# sensorNodev5.net
KiCad netlist of a schematic drawn in EAGLE
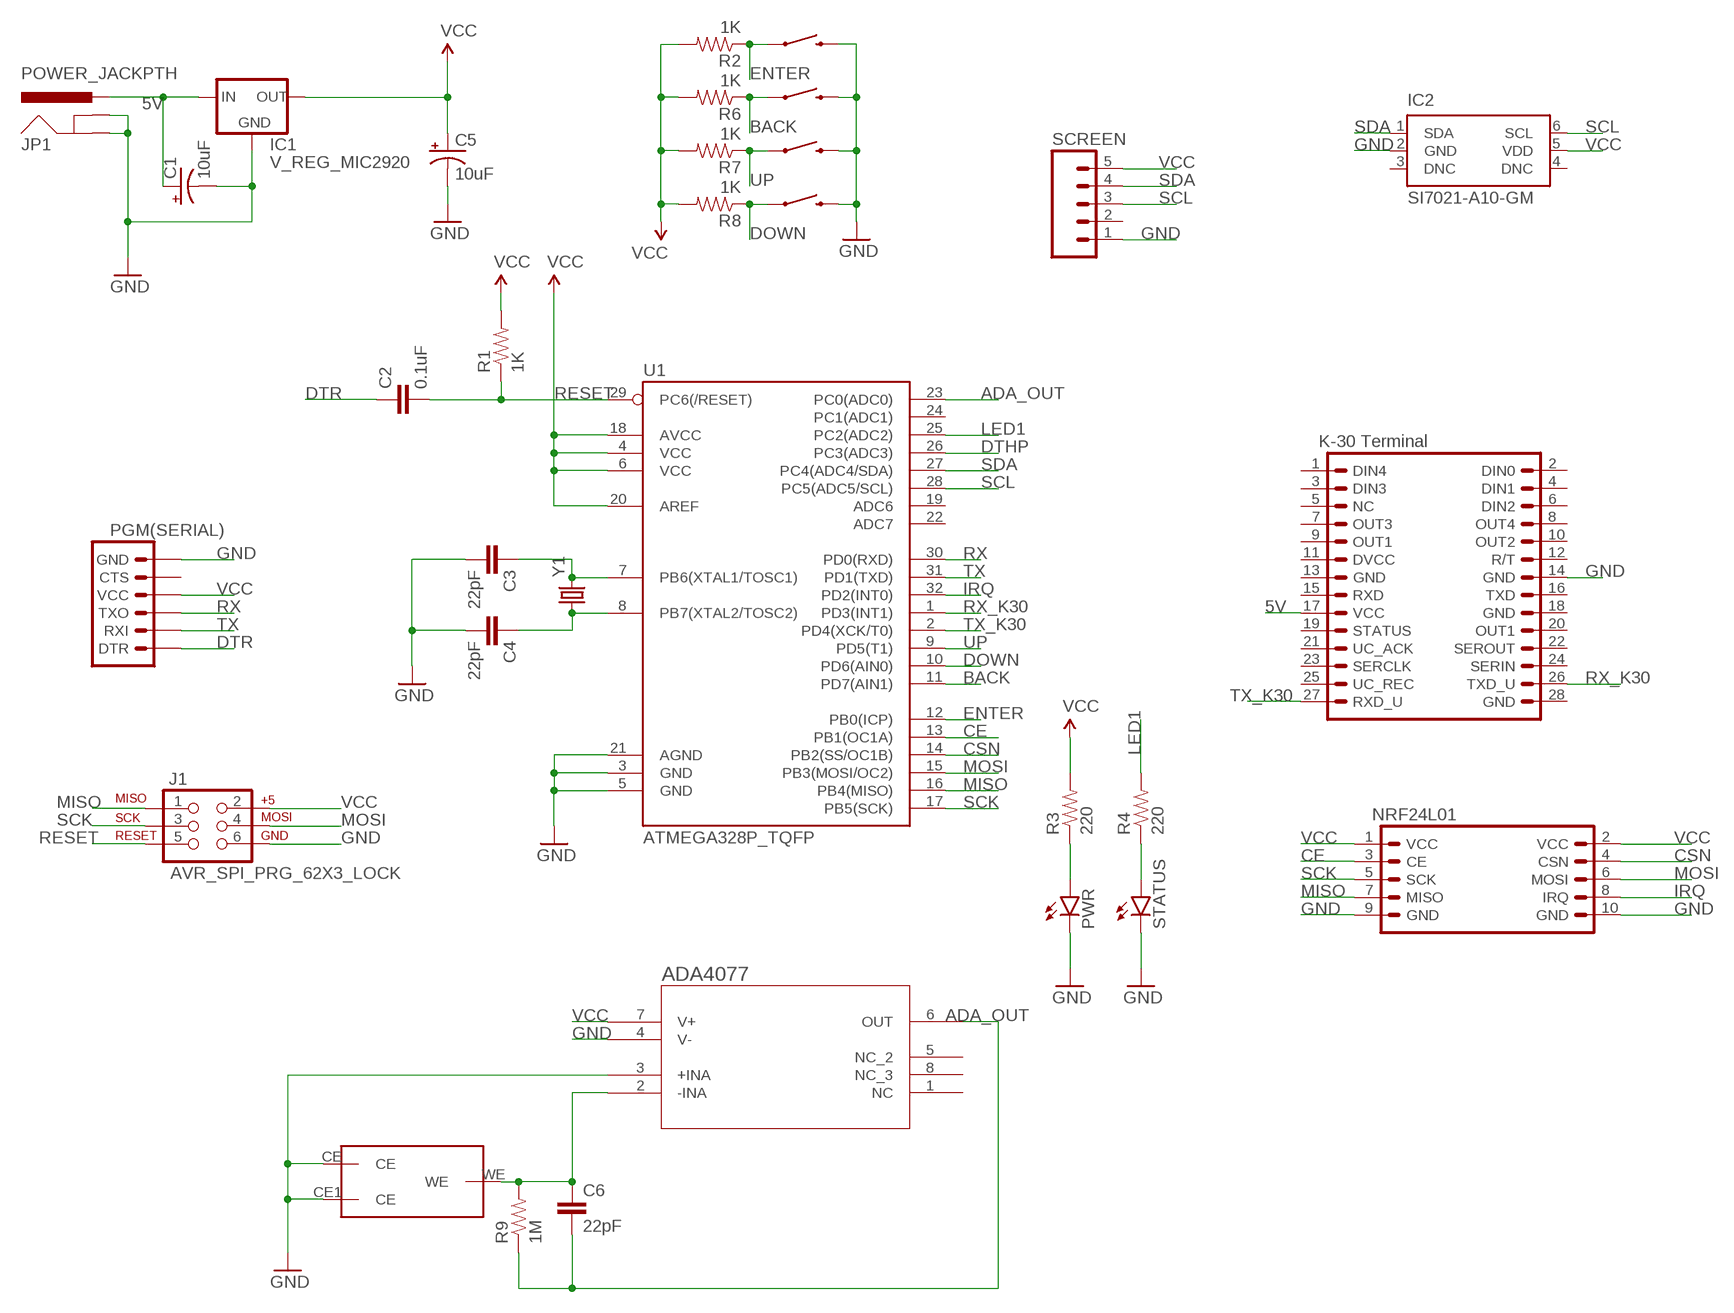
[diagram p0: schematic, sheet 1]

(export (version "E")
  (design (tool "Eeschema 10.0.6"))
  (components
    (comp (ref "BACK")
      (value "SWITCH-MOMENTARY-2PTH")
      (footprint "eagle-import:TACTILE-PTH")
      (libsource (lib "eagle-import") (part "SWITCH-MOMENTARY-2PTH"))
    )
    (comp (ref "C1")
      (value "10uF")
      (footprint "eagle-import:CPOL-RADIAL-10UF-25V")
      (libsource (lib "eagle-import") (part "CAP_POLPTH2"))
    )
    (comp (ref "C2")
      (value "0.1uF")
      (footprint "eagle-import:0603-CAP")
      (libsource (lib "eagle-import") (part "0.1UF-25V(+80/-20%)(0603)"))
    )
    (comp (ref "C3")
      (value "22pF")
      (footprint "eagle-import:0603-CAP")
      (libsource (lib "eagle-import") (part "22PF-50V-5%(0603)"))
    )
    (comp (ref "C4")
      (value "22pF")
      (footprint "eagle-import:0603-CAP")
      (libsource (lib "eagle-import") (part "22PF-50V-5%(0603)"))
    )
    (comp (ref "C5")
      (value "10uF")
      (footprint "eagle-import:CPOL-RADIAL-10UF-25V")
      (libsource (lib "eagle-import") (part "CAP_POLPTH2"))
    )
    (comp (ref "C6")
      (value "22pF")
      (footprint "eagle-import:0603-CAP")
      (libsource (lib "eagle-import") (part "22PF-50V-5%(0603)"))
    )
    (comp (ref "DOWN")
      (value "SWITCH-MOMENTARY-2PTH")
      (footprint "eagle-import:TACTILE-PTH")
      (libsource (lib "eagle-import") (part "SWITCH-MOMENTARY-2PTH"))
    )
    (comp (ref "ENTER")
      (value "SWITCH-MOMENTARY-2PTH")
      (footprint "eagle-import:TACTILE-PTH")
      (libsource (lib "eagle-import") (part "SWITCH-MOMENTARY-2PTH"))
    )
    (comp (ref "IC1")
      (value "V_REG_MIC2920")
      (footprint "eagle-import:SOT223")
      (libsource (lib "eagle-import") (part "V_REG_MIC2920"))
    )
    (comp (ref "IC2")
      (value "SI7021-A10-GM")
      (footprint "eagle-import:DFN6-3X3")
      (fields (field (name "MF") "Silicon Labs") (field (name "MPN") "Si7021-A10-GM"))
      (libsource (lib "eagle-import") (part "SI7021-A10-GM"))
    )
    (comp (ref "J1")
      (value "AVR_SPI_PRG_62X3_LOCK")
      (footprint "eagle-import:2X3_LOCK")
      (libsource (lib "eagle-import") (part "AVR_SPI_PRG_62X3_LOCK"))
    )
    (comp (ref "JP1")
      (value "POWER_JACKPTH")
      (footprint "eagle-import:POWER_JACK_PTH")
      (libsource (lib "eagle-import") (part "POWER_JACKPTH"))
    )
    (comp (ref "JP3")
      (value "K-30K-30")
      (footprint "eagle-import:K-30")
      (libsource (lib "eagle-import") (part "K-30K-30"))
    )
    (comp (ref "PGM(SERIAL)")
      (value "ARDUINO_SERIAL_PROGRAMPTH")
      (footprint "eagle-import:1X06")
      (libsource (lib "eagle-import") (part "ARDUINO_SERIAL_PROGRAMPTH"))
    )
    (comp (ref "PWR")
      (value "LED0603")
      (footprint "eagle-import:LED-0603")
      (libsource (lib "eagle-import") (part "LED0603"))
    )
    (comp (ref "R1")
      (value "1K")
      (footprint "eagle-import:0603-RES")
      (libsource (lib "eagle-import") (part "1KOHM-1/10W-1%(0603)"))
    )
    (comp (ref "R2")
      (value "1K")
      (footprint "eagle-import:0603-RES")
      (libsource (lib "eagle-import") (part "1KOHM-1/10W-1%(0603)"))
    )
    (comp (ref "R3")
      (value "220")
      (footprint "eagle-import:0603-RES")
      (libsource (lib "eagle-import") (part "1KOHM-1/10W-1%(0603)"))
    )
    (comp (ref "R4")
      (value "220")
      (footprint "eagle-import:0603-RES")
      (libsource (lib "eagle-import") (part "1KOHM-1/10W-1%(0603)"))
    )
    (comp (ref "R6")
      (value "1K")
      (footprint "eagle-import:0603-RES")
      (libsource (lib "eagle-import") (part "1KOHM-1/10W-1%(0603)"))
    )
    (comp (ref "R7")
      (value "1K")
      (footprint "eagle-import:0603-RES")
      (libsource (lib "eagle-import") (part "1KOHM-1/10W-1%(0603)"))
    )
    (comp (ref "R8")
      (value "1K")
      (footprint "eagle-import:0603-RES")
      (libsource (lib "eagle-import") (part "1KOHM-1/10W-1%(0603)"))
    )
    (comp (ref "R9")
      (value "1M")
      (footprint "eagle-import:0603-RES")
      (libsource (lib "eagle-import") (part "1KOHM-1/10W-1%(0603)"))
    )
    (comp (ref "SCREEN")
      (value "M05PTH")
      (footprint "eagle-import:1X05")
      (libsource (lib "eagle-import") (part "M05PTH"))
    )
    (comp (ref "STATUS")
      (value "LED0603")
      (footprint "eagle-import:LED-0603")
      (libsource (lib "eagle-import") (part "LED0603"))
    )
    (comp (ref "U$1")
      (value "TGS5042A")
      (footprint "eagle-import:TGS5042")
      (libsource (lib "eagle-import") (part "TGS5042A"))
    )
    (comp (ref "U$2")
      (value "NRF24L01")
      (footprint "eagle-import:NRF24L01")
      (libsource (lib "eagle-import") (part "NRF24L01"))
    )
    (comp (ref "U1")
      (value "ATMEGA328P_TQFP")
      (footprint "eagle-import:TQFP32-08")
      (libsource (lib "eagle-import") (part "ATMEGA328P_TQFP"))
    )
    (comp (ref "U2")
      (value "ADA4077-1ARZ")
      (footprint "eagle-import:R_8")
      (libsource (lib "eagle-import") (part "ADA4077-1ARZ"))
    )
    (comp (ref "UP")
      (value "SWITCH-MOMENTARY-2PTH")
      (footprint "eagle-import:TACTILE-PTH")
      (libsource (lib "eagle-import") (part "SWITCH-MOMENTARY-2PTH"))
    )
    (comp (ref "Y1")
      (value "CRYSTALHC49US")
      (footprint "eagle-import:HC49US")
      (libsource (lib "eagle-import") (part "CRYSTALHC49US"))
    )
  )
  (nets
    (net (code "1") (name "/5V") (class "Default")
      (node (ref "C1") (pin "1") (pinfunction "+_1") (pintype "passive"))
      (node (ref "IC1") (pin "1") (pinfunction "IN_1") (pintype "input"))
      (node (ref "JP1") (pin "PWR") (pinfunction "PWR_PWR") (pintype "bidirectional"))
      (node (ref "JP3") (pin "17") (pinfunction "VCC_17") (pintype "bidirectional"))
    )
    (net (code "2") (name "/ADA_OUT") (class "Default")
      (node (ref "C6") (pin "2") (pinfunction "2_2") (pintype "passive"))
      (node (ref "R9") (pin "1") (pinfunction "1_1") (pintype "passive"))
      (node (ref "U1") (pin "23") (pinfunction "PC0(ADC0)_23") (pintype "bidirectional"))
      (node (ref "U2") (pin "6") (pinfunction "OUT_6") (pintype "passive"))
    )
    (net (code "3") (name "/BACK") (class "Default")
      (node (ref "BACK") (pin "1") (pinfunction "1_1") (pintype "passive"))
      (node (ref "R6") (pin "1") (pinfunction "1_1") (pintype "passive"))
      (node (ref "U1") (pin "11") (pinfunction "PD7(AIN1)_11") (pintype "bidirectional"))
    )
    (net (code "4") (name "/CE") (class "Default")
      (node (ref "U$2") (pin "3") (pinfunction "CE_3") (pintype "bidirectional"))
      (node (ref "U1") (pin "13") (pinfunction "PB1(OC1A)_13") (pintype "bidirectional"))
    )
    (net (code "5") (name "/CSN") (class "Default")
      (node (ref "U$2") (pin "4") (pinfunction "CSN_4") (pintype "bidirectional"))
      (node (ref "U1") (pin "14") (pinfunction "PB2(SS/OC1B)_14") (pintype "bidirectional"))
    )
    (net (code "6") (name "/DOWN") (class "Default")
      (node (ref "DOWN") (pin "1") (pinfunction "1_1") (pintype "passive"))
      (node (ref "R8") (pin "1") (pinfunction "1_1") (pintype "passive"))
      (node (ref "U1") (pin "10") (pinfunction "PD6(AIN0)_10") (pintype "bidirectional"))
    )
    (net (code "7") (name "/DTHP") (class "Default")
      (node (ref "U1") (pin "26") (pinfunction "PC3(ADC3)_26") (pintype "bidirectional"))
    )
    (net (code "8") (name "/DTR") (class "Default")
      (node (ref "C2") (pin "1") (pinfunction "1_1") (pintype "passive"))
      (node (ref "PGM(SERIAL)") (pin "1") (pinfunction "DTR_1") (pintype "passive"))
    )
    (net (code "9") (name "/ENTER") (class "Default")
      (node (ref "ENTER") (pin "1") (pinfunction "1_1") (pintype "passive"))
      (node (ref "R2") (pin "1") (pinfunction "1_1") (pintype "passive"))
      (node (ref "U1") (pin "12") (pinfunction "PB0(ICP)_12") (pintype "bidirectional"))
    )
    (net (code "10") (name "/IRQ") (class "Default")
      (node (ref "U$2") (pin "8") (pinfunction "IRQ_8") (pintype "bidirectional"))
      (node (ref "U1") (pin "32") (pinfunction "PD2(INT0)_32") (pintype "bidirectional"))
    )
    (net (code "11") (name "/LED1") (class "Default")
      (node (ref "R4") (pin "2") (pinfunction "2_2") (pintype "passive"))
      (node (ref "U1") (pin "25") (pinfunction "PC2(ADC2)_25") (pintype "bidirectional"))
    )
    (net (code "12") (name "/MISO") (class "Default")
      (node (ref "J1") (pin "1") (pinfunction "1_1") (pintype "passive"))
      (node (ref "U$2") (pin "7") (pinfunction "MISO_7") (pintype "bidirectional"))
      (node (ref "U1") (pin "16") (pinfunction "PB4(MISO)_16") (pintype "bidirectional"))
    )
    (net (code "13") (name "/MOSI") (class "Default")
      (node (ref "J1") (pin "4") (pinfunction "4_4") (pintype "passive"))
      (node (ref "U$2") (pin "6") (pinfunction "MOSI_6") (pintype "bidirectional"))
      (node (ref "U1") (pin "15") (pinfunction "PB3(MOSI/OC2)_15") (pintype "bidirectional"))
    )
    (net (code "14") (name "/RESET") (class "Default")
      (node (ref "C2") (pin "2") (pinfunction "2_2") (pintype "passive"))
      (node (ref "J1") (pin "5") (pinfunction "5_5") (pintype "passive"))
      (node (ref "R1") (pin "1") (pinfunction "1_1") (pintype "passive"))
      (node (ref "U1") (pin "29") (pinfunction "PC6(/RESET)_29") (pintype "bidirectional"))
    )
    (net (code "15") (name "/RX") (class "Default")
      (node (ref "PGM(SERIAL)") (pin "3") (pinfunction "TXO_3") (pintype "passive"))
      (node (ref "U1") (pin "30") (pinfunction "PD0(RXD)_30") (pintype "bidirectional"))
    )
    (net (code "16") (name "/RX_K30") (class "Default")
      (node (ref "JP3") (pin "26") (pinfunction "TXD_U_26") (pintype "bidirectional"))
      (node (ref "U1") (pin "1") (pinfunction "PD3(INT1)_1") (pintype "bidirectional"))
    )
    (net (code "17") (name "/SCK") (class "Default")
      (node (ref "J1") (pin "3") (pinfunction "3_3") (pintype "passive"))
      (node (ref "U$2") (pin "5") (pinfunction "SCK_5") (pintype "bidirectional"))
      (node (ref "U1") (pin "17") (pinfunction "PB5(SCK)_17") (pintype "bidirectional"))
    )
    (net (code "18") (name "/SCL") (class "Default")
      (node (ref "IC2") (pin "6") (pinfunction "SCL_6") (pintype "input"))
      (node (ref "SCREEN") (pin "3") (pinfunction "3_3") (pintype "passive"))
      (node (ref "U1") (pin "28") (pinfunction "PC5(ADC5/SCL)_28") (pintype "bidirectional"))
    )
    (net (code "19") (name "/SDA") (class "Default")
      (node (ref "IC2") (pin "1") (pinfunction "SDA_1") (pintype "bidirectional"))
      (node (ref "SCREEN") (pin "4") (pinfunction "4_4") (pintype "passive"))
      (node (ref "U1") (pin "27") (pinfunction "PC4(ADC4/SDA)_27") (pintype "bidirectional"))
    )
    (net (code "20") (name "/TX") (class "Default")
      (node (ref "PGM(SERIAL)") (pin "2") (pinfunction "RXI_2") (pintype "passive"))
      (node (ref "U1") (pin "31") (pinfunction "PD1(TXD)_31") (pintype "bidirectional"))
    )
    (net (code "21") (name "/TX_K30") (class "Default")
      (node (ref "JP3") (pin "27") (pinfunction "RXD_U_27") (pintype "bidirectional"))
      (node (ref "U1") (pin "2") (pinfunction "PD4(XCK/T0)_2") (pintype "bidirectional"))
    )
    (net (code "22") (name "/UP") (class "Default")
      (node (ref "R7") (pin "1") (pinfunction "1_1") (pintype "passive"))
      (node (ref "U1") (pin "9") (pinfunction "PD5(T1)_9") (pintype "bidirectional"))
      (node (ref "UP") (pin "1") (pinfunction "1_1") (pintype "passive"))
    )
    (net (code "23") (name "GND") (class "Default")
      (node (ref "BACK") (pin "3") (pinfunction "2_3") (pintype "passive"))
      (node (ref "C1") (pin "2") (pinfunction "-_2") (pintype "passive"))
      (node (ref "C3") (pin "2") (pinfunction "2_2") (pintype "passive"))
      (node (ref "C4") (pin "2") (pinfunction "2_2") (pintype "passive"))
      (node (ref "C5") (pin "2") (pinfunction "-_2") (pintype "passive"))
      (node (ref "DOWN") (pin "3") (pinfunction "2_3") (pintype "passive"))
      (node (ref "ENTER") (pin "3") (pinfunction "2_3") (pintype "passive"))
      (node (ref "IC1") (pin "2") (pinfunction "GND_2") (pintype "input"))
      (node (ref "IC2") (pin "2") (pinfunction "GND_2") (pintype "power_in"))
      (node (ref "J1") (pin "6") (pinfunction "6_6") (pintype "passive"))
      (node (ref "JP1") (pin "GND") (pinfunction "GND_GND") (pintype "bidirectional"))
      (node (ref "JP1") (pin "GNDBREAK") (pinfunction "GNDBREAK_GNDBREAK") (pintype "bidirectional"))
      (node (ref "JP3") (pin "14") (pinfunction "GND_14") (pintype "bidirectional"))
      (node (ref "PGM(SERIAL)") (pin "6") (pinfunction "GND_6") (pintype "passive"))
      (node (ref "PWR") (pin "C") (pinfunction "C_C") (pintype "passive"))
      (node (ref "SCREEN") (pin "1") (pinfunction "1_1") (pintype "passive"))
      (node (ref "STATUS") (pin "C") (pinfunction "C_C") (pintype "passive"))
      (node (ref "U$1") (pin "CE") (pinfunction "CE_CE") (pintype "bidirectional"))
      (node (ref "U$1") (pin "CE1") (pinfunction "CE_CE1") (pintype "bidirectional"))
      (node (ref "U$2") (pin "10") (pinfunction "GND_10") (pintype "bidirectional"))
      (node (ref "U$2") (pin "9") (pinfunction "GND_9") (pintype "bidirectional"))
      (node (ref "U1") (pin "21") (pinfunction "AGND_21") (pintype "bidirectional"))
      (node (ref "U1") (pin "3") (pinfunction "GND_3") (pintype "bidirectional"))
      (node (ref "U1") (pin "5") (pinfunction "GND_5") (pintype "bidirectional"))
      (node (ref "U2") (pin "3") (pinfunction "+INA_3") (pintype "passive"))
      (node (ref "U2") (pin "4") (pinfunction "V-_4") (pintype "passive"))
      (node (ref "UP") (pin "3") (pinfunction "2_3") (pintype "passive"))
    )
    (net (code "24") (name "Net-(PWR-PadA)") (class "Default")
      (node (ref "PWR") (pin "A") (pinfunction "A_A") (pintype "passive"))
      (node (ref "R3") (pin "1") (pinfunction "1_1") (pintype "passive"))
    )
    (net (code "25") (name "Net-(R4-Pad1)") (class "Default")
      (node (ref "R4") (pin "1") (pinfunction "1_1") (pintype "passive"))
      (node (ref "STATUS") (pin "A") (pinfunction "A_A") (pintype "passive"))
    )
    (net (code "26") (name "Net-(U1-PB6(XTAL1{slash}TOSC1))") (class "Default")
      (node (ref "C3") (pin "1") (pinfunction "1_1") (pintype "passive"))
      (node (ref "U1") (pin "7") (pinfunction "PB6(XTAL1/TOSC1)_7") (pintype "bidirectional"))
      (node (ref "Y1") (pin "2") (pinfunction "2_2") (pintype "passive"))
    )
    (net (code "27") (name "Net-(U1-PB7(XTAL2{slash}TOSC2))") (class "Default")
      (node (ref "C4") (pin "1") (pinfunction "1_1") (pintype "passive"))
      (node (ref "U1") (pin "8") (pinfunction "PB7(XTAL2/TOSC2)_8") (pintype "bidirectional"))
      (node (ref "Y1") (pin "1") (pinfunction "1_1") (pintype "passive"))
    )
    (net (code "28") (name "Net-(U2--INA)") (class "Default")
      (node (ref "C6") (pin "1") (pinfunction "1_1") (pintype "passive"))
      (node (ref "R9") (pin "2") (pinfunction "2_2") (pintype "passive"))
      (node (ref "U$1") (pin "WE") (pinfunction "WE_WE") (pintype "bidirectional"))
      (node (ref "U2") (pin "2") (pinfunction "-INA_2") (pintype "passive"))
    )
    (net (code "29") (name "VCC") (class "Default")
      (node (ref "C5") (pin "1") (pinfunction "+_1") (pintype "passive"))
      (node (ref "IC1") (pin "3") (pinfunction "OUT_3") (pintype "output"))
      (node (ref "IC2") (pin "5") (pinfunction "VDD_5") (pintype "power_in"))
      (node (ref "J1") (pin "2") (pinfunction "2_2") (pintype "passive"))
      (node (ref "PGM(SERIAL)") (pin "4") (pinfunction "VCC_4") (pintype "passive"))
      (node (ref "R1") (pin "2") (pinfunction "2_2") (pintype "passive"))
      (node (ref "R2") (pin "2") (pinfunction "2_2") (pintype "passive"))
      (node (ref "R3") (pin "2") (pinfunction "2_2") (pintype "passive"))
      (node (ref "R6") (pin "2") (pinfunction "2_2") (pintype "passive"))
      (node (ref "R7") (pin "2") (pinfunction "2_2") (pintype "passive"))
      (node (ref "R8") (pin "2") (pinfunction "2_2") (pintype "passive"))
      (node (ref "SCREEN") (pin "5") (pinfunction "5_5") (pintype "passive"))
      (node (ref "U$2") (pin "1") (pinfunction "VCC_1") (pintype "bidirectional"))
      (node (ref "U$2") (pin "2") (pinfunction "VCC_2") (pintype "bidirectional"))
      (node (ref "U1") (pin "18") (pinfunction "AVCC_18") (pintype "bidirectional"))
      (node (ref "U1") (pin "20") (pinfunction "AREF_20") (pintype "bidirectional"))
      (node (ref "U1") (pin "4") (pinfunction "VCC_4") (pintype "bidirectional"))
      (node (ref "U1") (pin "6") (pinfunction "VCC_6") (pintype "bidirectional"))
      (node (ref "U2") (pin "7") (pinfunction "V+_7") (pintype "passive"))
    )
    (net (code "30") (name "unconnected-(IC2-DNC-Pad3)") (class "Default")
      (node (ref "IC2") (pin "3") (pinfunction "DNC_3") (pintype "no_connect"))
    )
    (net (code "31") (name "unconnected-(IC2-DNC-Pad4)") (class "Default")
      (node (ref "IC2") (pin "4") (pinfunction "DNC_4") (pintype "no_connect"))
    )
    (net (code "32") (name "unconnected-(JP3-DIN0-Pad2)") (class "Default")
      (node (ref "JP3") (pin "2") (pinfunction "DIN0_2") (pintype "bidirectional"))
    )
    (net (code "33") (name "unconnected-(JP3-DIN1-Pad4)") (class "Default")
      (node (ref "JP3") (pin "4") (pinfunction "DIN1_4") (pintype "bidirectional"))
    )
    (net (code "34") (name "unconnected-(JP3-DIN2-Pad6)") (class "Default")
      (node (ref "JP3") (pin "6") (pinfunction "DIN2_6") (pintype "bidirectional"))
    )
    (net (code "35") (name "unconnected-(JP3-DIN3-Pad3)") (class "Default")
      (node (ref "JP3") (pin "3") (pinfunction "DIN3_3") (pintype "bidirectional"))
    )
    (net (code "36") (name "unconnected-(JP3-DIN4-Pad1)") (class "Default")
      (node (ref "JP3") (pin "1") (pinfunction "DIN4_1") (pintype "bidirectional"))
    )
    (net (code "37") (name "unconnected-(JP3-DVCC-Pad11)") (class "Default")
      (node (ref "JP3") (pin "11") (pinfunction "DVCC_11") (pintype "bidirectional"))
    )
    (net (code "38") (name "unconnected-(JP3-GND-Pad13)") (class "Default")
      (node (ref "JP3") (pin "13") (pinfunction "GND_13") (pintype "bidirectional"))
    )
    (net (code "39") (name "unconnected-(JP3-GND-Pad18)") (class "Default")
      (node (ref "JP3") (pin "18") (pinfunction "GND_18") (pintype "bidirectional"))
    )
    (net (code "40") (name "unconnected-(JP3-GND-Pad28)") (class "Default")
      (node (ref "JP3") (pin "28") (pinfunction "GND_28") (pintype "bidirectional"))
    )
    (net (code "41") (name "unconnected-(JP3-NC-Pad5)") (class "Default")
      (node (ref "JP3") (pin "5") (pinfunction "NC_5") (pintype "bidirectional"))
    )
    (net (code "42") (name "unconnected-(JP3-OUT1-Pad9)") (class "Default")
      (node (ref "JP3") (pin "9") (pinfunction "OUT1_9") (pintype "bidirectional"))
    )
    (net (code "43") (name "unconnected-(JP3-OUT1-Pad20)") (class "Default")
      (node (ref "JP3") (pin "20") (pinfunction "OUT1_20") (pintype "bidirectional"))
    )
    (net (code "44") (name "unconnected-(JP3-OUT2-Pad10)") (class "Default")
      (node (ref "JP3") (pin "10") (pinfunction "OUT2_10") (pintype "bidirectional"))
    )
    (net (code "45") (name "unconnected-(JP3-OUT3-Pad7)") (class "Default")
      (node (ref "JP3") (pin "7") (pinfunction "OUT3_7") (pintype "bidirectional"))
    )
    (net (code "46") (name "unconnected-(JP3-OUT4-Pad8)") (class "Default")
      (node (ref "JP3") (pin "8") (pinfunction "OUT4_8") (pintype "bidirectional"))
    )
    (net (code "47") (name "unconnected-(JP3-RXD-Pad15)") (class "Default")
      (node (ref "JP3") (pin "15") (pinfunction "RXD_15") (pintype "bidirectional"))
    )
    (net (code "48") (name "unconnected-(JP3-R{slash}T-Pad12)") (class "Default")
      (node (ref "JP3") (pin "12") (pinfunction "R/T_12") (pintype "bidirectional"))
    )
    (net (code "49") (name "unconnected-(JP3-SERCLK-Pad23)") (class "Default")
      (node (ref "JP3") (pin "23") (pinfunction "SERCLK_23") (pintype "bidirectional"))
    )
    (net (code "50") (name "unconnected-(JP3-SERIN-Pad24)") (class "Default")
      (node (ref "JP3") (pin "24") (pinfunction "SERIN_24") (pintype "bidirectional"))
    )
    (net (code "51") (name "unconnected-(JP3-SEROUT-Pad22)") (class "Default")
      (node (ref "JP3") (pin "22") (pinfunction "SEROUT_22") (pintype "bidirectional"))
    )
    (net (code "52") (name "unconnected-(JP3-STATUS-Pad19)") (class "Default")
      (node (ref "JP3") (pin "19") (pinfunction "STATUS_19") (pintype "bidirectional"))
    )
    (net (code "53") (name "unconnected-(JP3-TXD-Pad16)") (class "Default")
      (node (ref "JP3") (pin "16") (pinfunction "TXD_16") (pintype "bidirectional"))
    )
    (net (code "54") (name "unconnected-(JP3-UC_ACK-Pad21)") (class "Default")
      (node (ref "JP3") (pin "21") (pinfunction "UC_ACK_21") (pintype "bidirectional"))
    )
    (net (code "55") (name "unconnected-(JP3-UC_REC-Pad25)") (class "Default")
      (node (ref "JP3") (pin "25") (pinfunction "UC_REC_25") (pintype "bidirectional"))
    )
    (net (code "56") (name "unconnected-(PGM(SERIAL)-CTS-Pad5)") (class "Default")
      (node (ref "PGM(SERIAL)") (pin "5") (pinfunction "CTS_5") (pintype "passive"))
    )
    (net (code "57") (name "unconnected-(SCREEN-Pad2)") (class "Default")
      (node (ref "SCREEN") (pin "2") (pinfunction "2_2") (pintype "passive"))
    )
    (net (code "58") (name "unconnected-(U1-ADC6-Pad19)") (class "Default")
      (node (ref "U1") (pin "19") (pinfunction "ADC6_19") (pintype "bidirectional"))
    )
    (net (code "59") (name "unconnected-(U1-ADC7-Pad22)") (class "Default")
      (node (ref "U1") (pin "22") (pinfunction "ADC7_22") (pintype "bidirectional"))
    )
    (net (code "60") (name "unconnected-(U1-PC1(ADC1)-Pad24)") (class "Default")
      (node (ref "U1") (pin "24") (pinfunction "PC1(ADC1)_24") (pintype "bidirectional"))
    )
    (net (code "61") (name "unconnected-(U2-NC-Pad1)") (class "Default")
      (node (ref "U2") (pin "1") (pinfunction "NC_1") (pintype "passive"))
    )
    (net (code "62") (name "unconnected-(U2-NC_2-Pad5)") (class "Default")
      (node (ref "U2") (pin "5") (pinfunction "NC_2_5") (pintype "passive"))
    )
    (net (code "63") (name "unconnected-(U2-NC_3-Pad8)") (class "Default")
      (node (ref "U2") (pin "8") (pinfunction "NC_3_8") (pintype "passive"))
    )
  )
)
